# Schematic.net
KiCad netlist of a schematic drawn in EAGLE
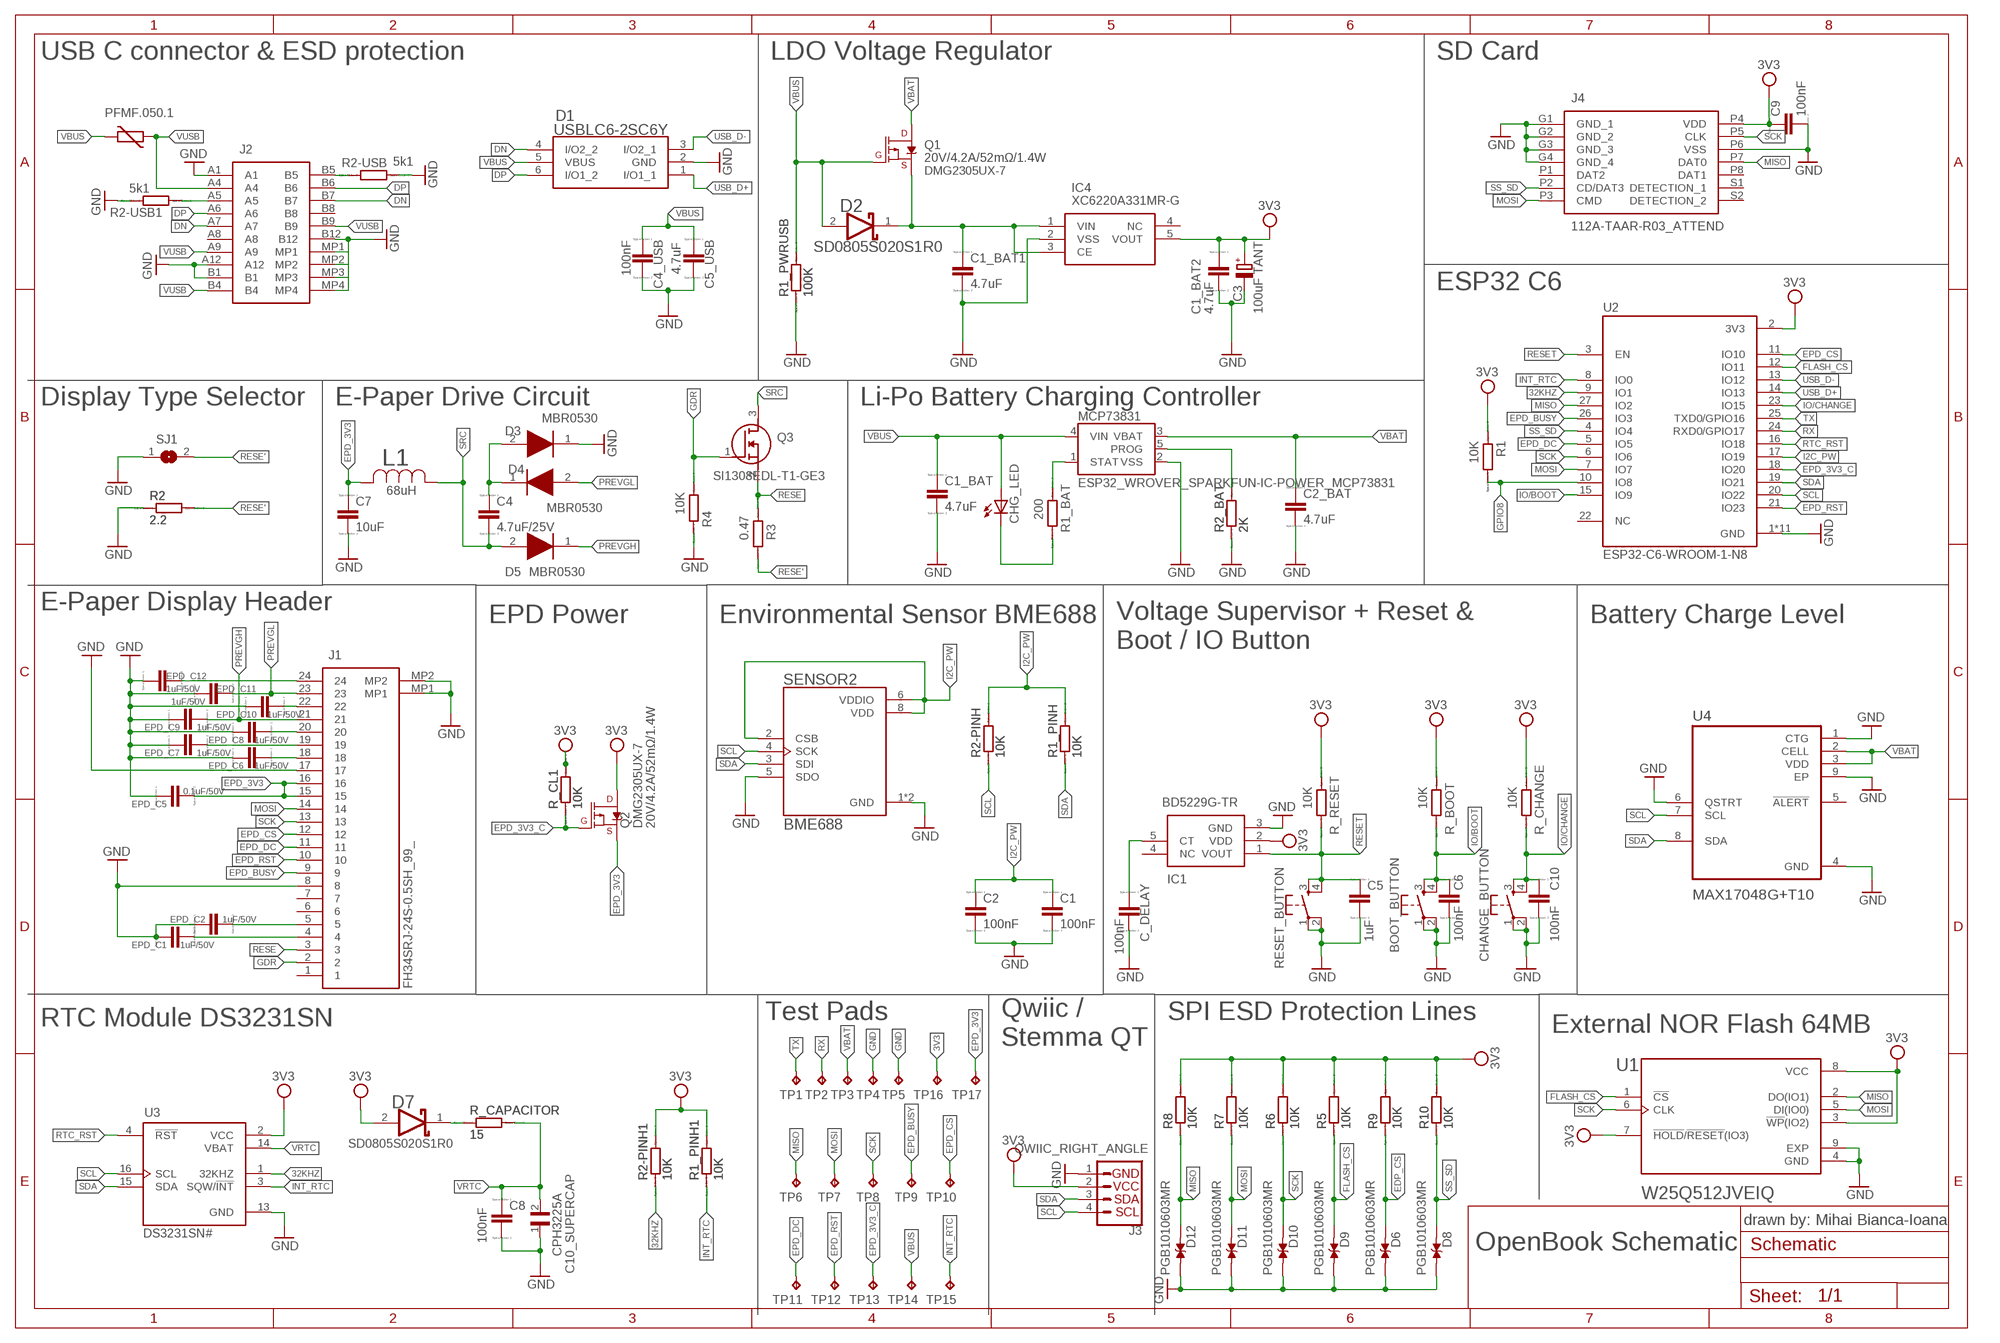
[diagram p0: schematic, sheet 1]

(export (version "E")
  (design (tool "Eeschema 10.0.6"))
  (components
    (comp (ref "BOOT_BUTTON")
      (value "BUTTON_CUSYOMV1")
      (footprint "eagle-import:MYBUTTON")
      (libsource (lib "eagle-import") (part "BUTTON_CUSYOMV1"))
    )
    (comp (ref "C1")
      (value "100nF")
      (footprint "eagle-import:ESP32_WROVER_EAGLE-LTSPICE_C0402")
      (libsource (lib "eagle-import") (part "ESP32_WROVER_EAGLE-LTSPICE_CC0402"))
    )
    (comp (ref "C1_BAT")
      (value "4.7uF")
      (footprint "eagle-import:ESP32_WROVER_EAGLE-LTSPICE_C0402")
      (libsource (lib "eagle-import") (part "ESP32_WROVER_EAGLE-LTSPICE_CC0402"))
    )
    (comp (ref "C1_BAT1")
      (value "4.7uF")
      (footprint "eagle-import:EAGLE-LTSPICE_C0402")
      (libsource (lib "eagle-import") (part "EAGLE-LTSPICE_CC0402"))
    )
    (comp (ref "C1_BAT2")
      (value "4.7uF")
      (footprint "eagle-import:EAGLE-LTSPICE_C0402")
      (libsource (lib "eagle-import") (part "EAGLE-LTSPICE_CC0402"))
    )
    (comp (ref "C2")
      (value "100nF")
      (footprint "eagle-import:ESP32_WROVER_EAGLE-LTSPICE_C0402")
      (libsource (lib "eagle-import") (part "ESP32_WROVER_EAGLE-LTSPICE_CC0402"))
    )
    (comp (ref "C2_BAT")
      (value "4.7uF")
      (footprint "eagle-import:ESP32_WROVER_EAGLE-LTSPICE_C0402")
      (libsource (lib "eagle-import") (part "ESP32_WROVER_EAGLE-LTSPICE_CC0402"))
    )
    (comp (ref "C3")
      (value "100uF TANT")
      (footprint "eagle-import:RCL_CT3528")
      (libsource (lib "eagle-import") (part "RCL_CPOL-EUCT3528"))
    )
    (comp (ref "C4")
      (value "4.7uF/25V")
      (footprint "eagle-import:ESP32_WROVER_EAGLE-LTSPICE_C0402")
      (libsource (lib "eagle-import") (part "ESP32_WROVER_EAGLE-LTSPICE_CC0402"))
    )
    (comp (ref "C4_USB")
      (value "100nF")
      (footprint "eagle-import:ESP32_WROVER_EAGLE-LTSPICE_C0402")
      (libsource (lib "eagle-import") (part "ESP32_WROVER_EAGLE-LTSPICE_CC0402"))
    )
    (comp (ref "C5")
      (value "1uF")
      (footprint "eagle-import:ESP32_WROVER_EAGLE-LTSPICE_C0402")
      (libsource (lib "eagle-import") (part "ESP32_WROVER_EAGLE-LTSPICE_CC0402"))
    )
    (comp (ref "C5_USB")
      (value "4.7uF")
      (footprint "eagle-import:ESP32_WROVER_EAGLE-LTSPICE_C0402")
      (libsource (lib "eagle-import") (part "ESP32_WROVER_EAGLE-LTSPICE_CC0402"))
    )
    (comp (ref "C6")
      (value "100nF")
      (footprint "eagle-import:ESP32_WROVER_EAGLE-LTSPICE_C0402")
      (libsource (lib "eagle-import") (part "ESP32_WROVER_EAGLE-LTSPICE_CC0402"))
    )
    (comp (ref "C7")
      (value "10uF")
      (footprint "eagle-import:ESP32_WROVER_EAGLE-LTSPICE_C0402")
      (libsource (lib "eagle-import") (part "ESP32_WROVER_EAGLE-LTSPICE_CC0402"))
    )
    (comp (ref "C8")
      (value "100nF")
      (footprint "eagle-import:ESP32_WROVER_EAGLE-LTSPICE_C0402")
      (libsource (lib "eagle-import") (part "ESP32_WROVER_EAGLE-LTSPICE_CC0402"))
    )
    (comp (ref "C9")
      (value "100nF")
      (footprint "eagle-import:ESP32_WROVER_EAGLE-LTSPICE_C0402")
      (libsource (lib "eagle-import") (part "ESP32_WROVER_EAGLE-LTSPICE_CC0402"))
    )
    (comp (ref "C10")
      (value "100nF")
      (footprint "eagle-import:ESP32_WROVER_EAGLE-LTSPICE_C0402")
      (libsource (lib "eagle-import") (part "ESP32_WROVER_EAGLE-LTSPICE_CC0402"))
    )
    (comp (ref "C10_SUPERCAP")
      (value "CPH3225A")
      (footprint "eagle-import:CAPCP3225X100N")
      (fields (field (name "MF") "Seiko Instruments"))
      (libsource (lib "eagle-import") (part "CPH3225A"))
    )
    (comp (ref "CHANGE_BUTTON")
      (value "BUTTON_CUSYOMV1")
      (footprint "eagle-import:MYBUTTON")
      (libsource (lib "eagle-import") (part "BUTTON_CUSYOMV1"))
    )
    (comp (ref "CHG_LED")
      (value "ADAFRUIT_LEDCHIP-LED0603")
      (footprint "eagle-import:ADAFRUIT_CHIP-LED0603")
      (libsource (lib "eagle-import") (part "ADAFRUIT_LEDCHIP-LED0603"))
    )
    (comp (ref "C_DELAY")
      (value "100nF")
      (footprint "eagle-import:ESP32_WROVER_EAGLE-LTSPICE_C0402")
      (libsource (lib "eagle-import") (part "ESP32_WROVER_EAGLE-LTSPICE_CC0402"))
    )
    (comp (ref "D1")
      (value "USBLC6-2SC6Y")
      (footprint "eagle-import:SOT95P280X145-6N")
      (fields
        (field (name "MF") "STMicroelectronics")
        (field (name "DETAILS") "USBLC6-2SC6Y")
        (field (name "NUME") "D1")
      )
      (libsource (lib "eagle-import") (part "USBLC6-2SC6Y"))
    )
    (comp (ref "D2")
      (value "ESP32_WROVER_AVX---SD0805S020S1R0_AVX_SD0805S020S1R0_0_0AVX_SD0805S020S1R0_0_0")
      (footprint "eagle-import:ESP32_WROVER_AVX---SD0805S020S1R0_AVX_SD0805S020S1R0_0")
      (fields
        (field (name "DIGIKEY_PART_NUMBER") "478-7800-1-ND")
        (field (name "MF") "AVX")
        (field (name "MOUSER_PART_NUMBER") "581-SD0805S020S1R0")
        (field (name "DETAILS") " SD0805S020S1R0")
      )
      (libsource (lib "eagle-import") (part "ESP32_WROVER_AVX---SD0805S020S1R0_AVX_SD0805S020S1R0_0_0AVX_SD0805S020S1R0_0_0"))
    )
    (comp (ref "D3")
      (value "MBR0530")
      (footprint "eagle-import:SOD3716X135N")
      (fields (field (name "MF") "ON Semiconductor"))
      (libsource (lib "eagle-import") (part "MBR0530"))
    )
    (comp (ref "D4")
      (value "MBR0530")
      (footprint "eagle-import:SOD3716X135N")
      (fields (field (name "MF") "ON Semiconductor"))
      (libsource (lib "eagle-import") (part "MBR0530"))
    )
    (comp (ref "D5")
      (value "MBR0530")
      (footprint "eagle-import:SOD3716X135N")
      (fields (field (name "MF") "ON Semiconductor"))
      (libsource (lib "eagle-import") (part "MBR0530"))
    )
    (comp (ref "D6")
      (value "PGB1010603MR")
      (footprint "eagle-import:DIOC1608X36N")
      (fields (field (name "MF") "Littelfuse Inc."))
      (libsource (lib "eagle-import") (part "PGB1010603MR"))
    )
    (comp (ref "D7")
      (value "ESP32_WROVER_AVX---SD0805S020S1R0_AVX_SD0805S020S1R0_0_0AVX_SD0805S020S1R0_0_0")
      (footprint "eagle-import:ESP32_WROVER_AVX---SD0805S020S1R0_AVX_SD0805S020S1R0_0")
      (fields
        (field (name "DIGIKEY_PART_NUMBER") "478-7800-1-ND")
        (field (name "MF") "AVX")
        (field (name "MOUSER_PART_NUMBER") "581-SD0805S020S1R0")
        (field (name "VALOARE") "SD0805S020S1R0")
      )
      (libsource (lib "eagle-import") (part "ESP32_WROVER_AVX---SD0805S020S1R0_AVX_SD0805S020S1R0_0_0AVX_SD0805S020S1R0_0_0"))
    )
    (comp (ref "D8")
      (value "PGB1010603MR")
      (footprint "eagle-import:DIOC1608X36N")
      (fields (field (name "MF") "Littelfuse Inc."))
      (libsource (lib "eagle-import") (part "PGB1010603MR"))
    )
    (comp (ref "D9")
      (value "PGB1010603MR")
      (footprint "eagle-import:DIOC1608X36N")
      (fields (field (name "MF") "Littelfuse Inc."))
      (libsource (lib "eagle-import") (part "PGB1010603MR"))
    )
    (comp (ref "D10")
      (value "PGB1010603MR")
      (footprint "eagle-import:DIOC1608X36N")
      (fields (field (name "MF") "Littelfuse Inc."))
      (libsource (lib "eagle-import") (part "PGB1010603MR"))
    )
    (comp (ref "D11")
      (value "PGB1010603MR")
      (footprint "eagle-import:DIOC1608X36N")
      (fields (field (name "MF") "Littelfuse Inc."))
      (libsource (lib "eagle-import") (part "PGB1010603MR"))
    )
    (comp (ref "D12")
      (value "PGB1010603MR")
      (footprint "eagle-import:DIOC1608X36N")
      (fields (field (name "MF") "Littelfuse Inc."))
      (libsource (lib "eagle-import") (part "PGB1010603MR"))
    )
    (comp (ref "EPD_C1")
      (value "1uF/50V")
      (footprint "eagle-import:ESP32_WROVER_EAGLE-LTSPICE_C0402")
      (libsource (lib "eagle-import") (part "ESP32_WROVER_EAGLE-LTSPICE_CC0402"))
    )
    (comp (ref "EPD_C2")
      (value "1uF/50V")
      (footprint "eagle-import:ESP32_WROVER_EAGLE-LTSPICE_C0402")
      (libsource (lib "eagle-import") (part "ESP32_WROVER_EAGLE-LTSPICE_CC0402"))
    )
    (comp (ref "EPD_C5")
      (value "0.1uF/50V")
      (footprint "eagle-import:ESP32_WROVER_EAGLE-LTSPICE_C0402")
      (libsource (lib "eagle-import") (part "ESP32_WROVER_EAGLE-LTSPICE_CC0402"))
    )
    (comp (ref "EPD_C6")
      (value "1uF/50V")
      (footprint "eagle-import:ESP32_WROVER_EAGLE-LTSPICE_C0402")
      (libsource (lib "eagle-import") (part "ESP32_WROVER_EAGLE-LTSPICE_CC0402"))
    )
    (comp (ref "EPD_C7")
      (value "1uF/50V")
      (footprint "eagle-import:ESP32_WROVER_EAGLE-LTSPICE_C0402")
      (libsource (lib "eagle-import") (part "ESP32_WROVER_EAGLE-LTSPICE_CC0402"))
    )
    (comp (ref "EPD_C8")
      (value "1uF/50V")
      (footprint "eagle-import:ESP32_WROVER_EAGLE-LTSPICE_C0402")
      (libsource (lib "eagle-import") (part "ESP32_WROVER_EAGLE-LTSPICE_CC0402"))
    )
    (comp (ref "EPD_C9")
      (value "1uF/50V")
      (footprint "eagle-import:ESP32_WROVER_EAGLE-LTSPICE_C0402")
      (libsource (lib "eagle-import") (part "ESP32_WROVER_EAGLE-LTSPICE_CC0402"))
    )
    (comp (ref "EPD_C10")
      (value "1uF/50V")
      (footprint "eagle-import:ESP32_WROVER_EAGLE-LTSPICE_C0402")
      (libsource (lib "eagle-import") (part "ESP32_WROVER_EAGLE-LTSPICE_CC0402"))
    )
    (comp (ref "EPD_C11")
      (value "1uF/50V")
      (footprint "eagle-import:ESP32_WROVER_EAGLE-LTSPICE_C0402")
      (libsource (lib "eagle-import") (part "ESP32_WROVER_EAGLE-LTSPICE_CC0402"))
    )
    (comp (ref "EPD_C12")
      (value "1uF/50V")
      (footprint "eagle-import:ESP32_WROVER_EAGLE-LTSPICE_C0402")
      (libsource (lib "eagle-import") (part "ESP32_WROVER_EAGLE-LTSPICE_CC0402"))
    )
    (comp (ref "IC1")
      (value "BD5229G-TR")
      (footprint "eagle-import:SOT95P280X125-5N")
      (fields (field (name "MOUSER_PART_NUMBER") "755-BD5229G-TR"))
      (libsource (lib "eagle-import") (part "BD5229G-TR"))
    )
    (comp (ref "IC4")
      (value "XC6220A331MR-G")
      (footprint "eagle-import:SOT95P280X120-5N")
      (fields (field (name "MOUSER_PART_NUMBER") "865-XC6220A331MR-G"))
      (libsource (lib "eagle-import") (part "XC6220A331MR-G"))
    )
    (comp (ref "J1")
      (value "FH34SRJ-24S-0.5SH_99_")
      (footprint "eagle-import:FH34SRJ24S05SH99")
      (fields
        (field (name "MANUFACTURER_PART_NUMBER") "FH34SRJ-24S-0.5SH(99)")
        (field (name "MOUSER_PART_NUMBER") "798-FH34SRJ24S05SH99")
      )
      (libsource (lib "eagle-import") (part "FH34SRJ-24S-0.5SH_99_"))
    )
    (comp (ref "J2")
      (value "SAMACSYS_PARTS_USB4110-GF-A")
      (footprint "eagle-import:SAMACSYS_PARTS_USB4110GFA")
      (fields
        (field (name "MANUFACTURER_PART_NUMBER") "USB4110-GF-A")
        (field (name "MOUSER_PART_NUMBER") "640-USB4110-GF-A")
      )
      (libsource (lib "eagle-import") (part "SAMACSYS_PARTS_USB4110-GF-A"))
    )
    (comp (ref "J3")
      (value "QWIIC_RIGHT_ANGLE")
      (footprint "eagle-import:JST04_1MM_RA")
      (libsource (lib "eagle-import") (part "QWIIC_CONNECTORJS-1MM"))
    )
    (comp (ref "J4")
      (value "112A-TAAR-R03_ATTEND")
      (footprint "eagle-import:112ATAARR03ATTEND")
      (fields (field (name "MANUFACTURER_PART_NUMBER") "112A-TAAR-R03 ATTEND"))
      (libsource (lib "eagle-import") (part "112A-TAAR-R03_ATTEND"))
    )
    (comp (ref "L1")
      (value "68uH")
      (footprint "eagle-import:IND_4828-WE-TPC_WRE")
      (fields
        (field (name "MANUFACTURER_PART_NUMBER") "744043680")
        (field (name "VALOARE") "68uH")
        (field (name "COPYRIGHT") "Copyright (C) 2024 Ultra Librarian. All rights reserved.")
      )
      (libsource (lib "eagle-import") (part "744043680IND_4828-WE-TPC_WRE"))
    )
    (comp (ref "MCP73831")
      (value "ESP32_WROVER_SPARKFUN-IC-POWER_MCP73831")
      (footprint "eagle-import:ESP32_WROVER_SPARKFUN-IC-POWER_SOT23-5")
      (libsource (lib "eagle-import") (part "ESP32_WROVER_SPARKFUN-IC-POWER_MCP73831"))
    )
    (comp (ref "PFMF.050.1")
      (value "ESP32C6_VARISTORCN1812")
      (footprint "eagle-import:ESP32C6_VARISTOR_CT_CN1812")
      (libsource (lib "eagle-import") (part "ESP32C6_VARISTORCN1812"))
    )
    (comp (ref "Q1")
      (value "20V/4.2A/52mΩ/1.4W")
      (footprint "eagle-import:ESP32_WROVER_SPARKFUN-DISCRETESEMI_SOT23-3")
      (fields (field (name "DETAILS") "DMG2305UX-7"))
      (libsource (lib "eagle-import") (part "ESP32_WROVER_SPARKFUN-DISCRETESEMI_MOSFET_PCH-DMG2305UX-7"))
    )
    (comp (ref "Q2")
      (value "20V/4.2A/52mΩ/1.4W")
      (footprint "eagle-import:ESP32_WROVER_SPARKFUN-DISCRETESEMI_SOT23-3")
      (fields (field (name "DETAILS") "DMG2305UX-7"))
      (libsource (lib "eagle-import") (part "ESP32_WROVER_SPARKFUN-DISCRETESEMI_MOSFET_PCH-DMG2305UX-7"))
    )
    (comp (ref "Q3")
      (value "SI1308EDL-T1-GE3")
      (footprint "eagle-import:SOT65P210X110-3N")
      (fields (field (name "MF") "Vishay Siliconix"))
      (libsource (lib "eagle-import") (part "SI1308EDL-T1-GE3"))
    )
    (comp (ref "R1")
      (value "10K")
      (footprint "eagle-import:ESP32_WROVER_EAGLE-LTSPICE_R0402")
      (libsource (lib "eagle-import") (part "ESP32_WROVER_EAGLE-LTSPICE_RR0402"))
    )
    (comp (ref "R1_BAT")
      (value "200")
      (footprint "eagle-import:ESP32_WROVER_EAGLE-LTSPICE_R0402")
      (libsource (lib "eagle-import") (part "ESP32_WROVER_EAGLE-LTSPICE_RR0402"))
    )
    (comp (ref "R1_PINH")
      (value "10K")
      (footprint "eagle-import:ESP32_WROVER_EAGLE-LTSPICE_R0402")
      (libsource (lib "eagle-import") (part "ESP32_WROVER_EAGLE-LTSPICE_RR0402"))
    )
    (comp (ref "R1_PINH1")
      (value "10K")
      (footprint "eagle-import:ESP32_WROVER_EAGLE-LTSPICE_R0402")
      (libsource (lib "eagle-import") (part "ESP32_WROVER_EAGLE-LTSPICE_RR0402"))
    )
    (comp (ref "R1_PWRUSB")
      (value "100K")
      (footprint "eagle-import:ESP32_WROVER_EAGLE-LTSPICE_R0402")
      (libsource (lib "eagle-import") (part "ESP32_WROVER_EAGLE-LTSPICE_RR0402"))
    )
    (comp (ref "R2")
      (value "2.2")
      (footprint "eagle-import:ESP32_WROVER_EAGLE-LTSPICE_R0402")
      (libsource (lib "eagle-import") (part "ESP32_WROVER_EAGLE-LTSPICE_RR0402"))
    )
    (comp (ref "R2-PINH")
      (value "10K")
      (footprint "eagle-import:ESP32_WROVER_EAGLE-LTSPICE_R0402")
      (libsource (lib "eagle-import") (part "ESP32_WROVER_EAGLE-LTSPICE_RR0402"))
    )
    (comp (ref "R2-PINH1")
      (value "10K")
      (footprint "eagle-import:ESP32_WROVER_EAGLE-LTSPICE_R0402")
      (libsource (lib "eagle-import") (part "ESP32_WROVER_EAGLE-LTSPICE_RR0402"))
    )
    (comp (ref "R2-USB")
      (value "5k1")
      (footprint "eagle-import:ESP32_WROVER_EAGLE-LTSPICE_R0402")
      (libsource (lib "eagle-import") (part "ESP32_WROVER_EAGLE-LTSPICE_RR0402"))
    )
    (comp (ref "R2-USB1")
      (value "5k1")
      (footprint "eagle-import:ESP32_WROVER_EAGLE-LTSPICE_R0402")
      (libsource (lib "eagle-import") (part "ESP32_WROVER_EAGLE-LTSPICE_RR0402"))
    )
    (comp (ref "R2_BAT")
      (value "2K")
      (footprint "eagle-import:ESP32_WROVER_EAGLE-LTSPICE_R0402")
      (libsource (lib "eagle-import") (part "ESP32_WROVER_EAGLE-LTSPICE_RR0402"))
    )
    (comp (ref "R3")
      (value "0.47")
      (footprint "eagle-import:ESP32_WROVER_EAGLE-LTSPICE_R0402")
      (libsource (lib "eagle-import") (part "ESP32_WROVER_EAGLE-LTSPICE_RR0402"))
    )
    (comp (ref "R4")
      (value "10K")
      (footprint "eagle-import:ESP32_WROVER_EAGLE-LTSPICE_R0402")
      (libsource (lib "eagle-import") (part "ESP32_WROVER_EAGLE-LTSPICE_RR0402"))
    )
    (comp (ref "R5")
      (value "10K")
      (footprint "eagle-import:ESP32_WROVER_EAGLE-LTSPICE_R0402")
      (libsource (lib "eagle-import") (part "ESP32_WROVER_EAGLE-LTSPICE_RR0402"))
    )
    (comp (ref "R6")
      (value "10K")
      (footprint "eagle-import:ESP32_WROVER_EAGLE-LTSPICE_R0402")
      (libsource (lib "eagle-import") (part "ESP32_WROVER_EAGLE-LTSPICE_RR0402"))
    )
    (comp (ref "R7")
      (value "10K")
      (footprint "eagle-import:ESP32_WROVER_EAGLE-LTSPICE_R0402")
      (libsource (lib "eagle-import") (part "ESP32_WROVER_EAGLE-LTSPICE_RR0402"))
    )
    (comp (ref "R8")
      (value "10K")
      (footprint "eagle-import:ESP32_WROVER_EAGLE-LTSPICE_R0402")
      (libsource (lib "eagle-import") (part "ESP32_WROVER_EAGLE-LTSPICE_RR0402"))
    )
    (comp (ref "R9")
      (value "10K")
      (footprint "eagle-import:ESP32_WROVER_EAGLE-LTSPICE_R0402")
      (libsource (lib "eagle-import") (part "ESP32_WROVER_EAGLE-LTSPICE_RR0402"))
    )
    (comp (ref "R10")
      (value "10K")
      (footprint "eagle-import:ESP32_WROVER_EAGLE-LTSPICE_R0402")
      (libsource (lib "eagle-import") (part "ESP32_WROVER_EAGLE-LTSPICE_RR0402"))
    )
    (comp (ref "RESET_BUTTON")
      (value "BUTTON_CUSYOMV1")
      (footprint "eagle-import:MYBUTTON")
      (libsource (lib "eagle-import") (part "BUTTON_CUSYOMV1"))
    )
    (comp (ref "R_BOOT")
      (value "10K")
      (footprint "eagle-import:ESP32_WROVER_EAGLE-LTSPICE_R0402")
      (libsource (lib "eagle-import") (part "ESP32_WROVER_EAGLE-LTSPICE_RR0402"))
    )
    (comp (ref "R_CAPACITOR")
      (value "15")
      (footprint "eagle-import:ESP32_WROVER_EAGLE-LTSPICE_R0402")
      (libsource (lib "eagle-import") (part "ESP32_WROVER_EAGLE-LTSPICE_RR0402"))
    )
    (comp (ref "R_CHANGE")
      (value "10K")
      (footprint "eagle-import:ESP32_WROVER_EAGLE-LTSPICE_R0402")
      (libsource (lib "eagle-import") (part "ESP32_WROVER_EAGLE-LTSPICE_RR0402"))
    )
    (comp (ref "R_CL1")
      (value "10K")
      (footprint "eagle-import:ESP32_WROVER_EAGLE-LTSPICE_R0402")
      (libsource (lib "eagle-import") (part "ESP32_WROVER_EAGLE-LTSPICE_RR0402"))
    )
    (comp (ref "R_RESET")
      (value "10K")
      (footprint "eagle-import:ESP32_WROVER_EAGLE-LTSPICE_R0402")
      (libsource (lib "eagle-import") (part "ESP32_WROVER_EAGLE-LTSPICE_RR0402"))
    )
    (comp (ref "SENSOR2")
      (value "BME688")
      (footprint "eagle-import:ESP32_WROVER_BME680_PSON80P300X300X100-8N")
      (fields (field (name "MF") "Bosch Sensortec") (field (name "MP") "BME680"))
      (libsource (lib "eagle-import") (part "ESP32_WROVER_BME680_BME680"))
    )
    (comp (ref "SJ1") (value "SJ") (footprint "eagle-import:SJ") (libsource (lib "eagle-import") (part "SJ")))
    (comp (ref "TP1")
      (value "TPTP20R")
      (footprint "eagle-import:TP20R")
      (libsource (lib "eagle-import") (part "TPTP20R"))
    )
    (comp (ref "TP2")
      (value "TPTP20R")
      (footprint "eagle-import:TP20R")
      (libsource (lib "eagle-import") (part "TPTP20R"))
    )
    (comp (ref "TP3")
      (value "TPTP20R")
      (footprint "eagle-import:TP20R")
      (libsource (lib "eagle-import") (part "TPTP20R"))
    )
    (comp (ref "TP4")
      (value "TPTP20R")
      (footprint "eagle-import:TP20R")
      (libsource (lib "eagle-import") (part "TPTP20R"))
    )
    (comp (ref "TP5")
      (value "TPTP20R")
      (footprint "eagle-import:TP20R")
      (libsource (lib "eagle-import") (part "TPTP20R"))
    )
    (comp (ref "TP6")
      (value "TPTP20R")
      (footprint "eagle-import:TP20R")
      (libsource (lib "eagle-import") (part "TPTP20R"))
    )
    (comp (ref "TP7")
      (value "TPTP20R")
      (footprint "eagle-import:TP20R")
      (libsource (lib "eagle-import") (part "TPTP20R"))
    )
    (comp (ref "TP8")
      (value "TPTP20R")
      (footprint "eagle-import:TP20R")
      (libsource (lib "eagle-import") (part "TPTP20R"))
    )
    (comp (ref "TP9")
      (value "TPTP20R")
      (footprint "eagle-import:TP20R")
      (libsource (lib "eagle-import") (part "TPTP20R"))
    )
    (comp (ref "TP10")
      (value "TPTP20R")
      (footprint "eagle-import:TP20R")
      (libsource (lib "eagle-import") (part "TPTP20R"))
    )
    (comp (ref "TP11")
      (value "TPTP20R")
      (footprint "eagle-import:TP20R")
      (libsource (lib "eagle-import") (part "TPTP20R"))
    )
    (comp (ref "TP12")
      (value "TPTP20R")
      (footprint "eagle-import:TP20R")
      (libsource (lib "eagle-import") (part "TPTP20R"))
    )
    (comp (ref "TP13")
      (value "TPTP20R")
      (footprint "eagle-import:TP20R")
      (libsource (lib "eagle-import") (part "TPTP20R"))
    )
    (comp (ref "TP14")
      (value "TPTP20R")
      (footprint "eagle-import:TP20R")
      (libsource (lib "eagle-import") (part "TPTP20R"))
    )
    (comp (ref "TP15")
      (value "TPTP20R")
      (footprint "eagle-import:TP20R")
      (libsource (lib "eagle-import") (part "TPTP20R"))
    )
    (comp (ref "TP16")
      (value "TPTP20R")
      (footprint "eagle-import:TP20R")
      (libsource (lib "eagle-import") (part "TPTP20R"))
    )
    (comp (ref "TP17")
      (value "TPTP20R")
      (footprint "eagle-import:TP20R")
      (libsource (lib "eagle-import") (part "TPTP20R"))
    )
    (comp (ref "U1")
      (value "W25Q512JVEIQ")
      (footprint "eagle-import:SON127P600X800X80-9N")
      (fields (field (name "MF") "Winbond Electronics"))
      (libsource (lib "eagle-import") (part "W25Q512JVEIQ"))
    )
    (comp (ref "U2")
      (value "ESP32-C6-WROOM-1-N8")
      (footprint "eagle-import:XCVR_ESP32-C6-WROOM-1-N8")
      (fields (field (name "MF") "Espressif Systems"))
      (libsource (lib "eagle-import") (part "ESP32-C6-WROOM-1-N8"))
    )
    (comp (ref "U3")
      (value "DS3231SN#")
      (footprint "eagle-import:SOIC127P1032X265-16N")
      (fields (field (name "MF") "Analog Devices"))
      (libsource (lib "eagle-import") (part "DS3231SN#"))
    )
    (comp (ref "U4")
      (value "MAX17048G+T10")
      (footprint "eagle-import:SON50P200X200X80-9N")
      (fields (field (name "MF") "Analog Devices"))
      (libsource (lib "eagle-import") (part "MAX17048G+T10"))
    )
  )
  (nets
    (net (code "1") (name "3V3") (class "Default")
      (node (ref "C1_BAT2") (pin "1") (pinfunction "1_1") (pintype "passive"))
      (node (ref "C3") (pin "+") (pinfunction "+_+") (pintype "passive"))
      (node (ref "C9") (pin "1") (pinfunction "1_1") (pintype "passive"))
      (node (ref "D7") (pin "2") (pinfunction "ANODE_2") (pintype "bidirectional"))
      (node (ref "IC1") (pin "2") (pinfunction "VDD_2") (pintype "bidirectional"))
      (node (ref "IC4") (pin "5") (pinfunction "VOUT_5") (pintype "bidirectional"))
      (node (ref "J3") (pin "2") (pinfunction "2_2") (pintype "power_in"))
      (node (ref "J4") (pin "P4") (pinfunction "VDD_P4") (pintype "bidirectional"))
      (node (ref "Q2") (pin "3") (pinfunction "D_3") (pintype "bidirectional"))
      (node (ref "R1") (pin "2") (pinfunction "2_2") (pintype "passive"))
      (node (ref "R10") (pin "2") (pinfunction "2_2") (pintype "passive"))
      (node (ref "R1_PINH1") (pin "2") (pinfunction "2_2") (pintype "passive"))
      (node (ref "R2-PINH1") (pin "2") (pinfunction "2_2") (pintype "passive"))
      (node (ref "R5") (pin "2") (pinfunction "2_2") (pintype "passive"))
      (node (ref "R6") (pin "2") (pinfunction "2_2") (pintype "passive"))
      (node (ref "R7") (pin "2") (pinfunction "2_2") (pintype "passive"))
      (node (ref "R8") (pin "2") (pinfunction "2_2") (pintype "passive"))
      (node (ref "R9") (pin "2") (pinfunction "2_2") (pintype "passive"))
      (node (ref "R_BOOT") (pin "2") (pinfunction "2_2") (pintype "passive"))
      (node (ref "R_CHANGE") (pin "2") (pinfunction "2_2") (pintype "passive"))
      (node (ref "R_CL1") (pin "2") (pinfunction "2_2") (pintype "passive"))
      (node (ref "R_RESET") (pin "2") (pinfunction "2_2") (pintype "passive"))
      (node (ref "TP16") (pin "TP") (pinfunction "TP_TP") (pintype "input"))
      (node (ref "U1") (pin "3") (pinfunction "~{WP}(IO2)_3") (pintype "bidirectional"))
      (node (ref "U1") (pin "7") (pinfunction "~{HOLD}/~{RESET}(IO3)_7") (pintype "bidirectional"))
      (node (ref "U1") (pin "8") (pinfunction "VCC_8") (pintype "power_in"))
      (node (ref "U2") (pin "2") (pinfunction "3V3_2") (pintype "power_in"))
      (node (ref "U3") (pin "2") (pinfunction "VCC_2") (pintype "power_in"))
    )
    (net (code "2") (name "32KHZ") (class "Default")
      (node (ref "R2-PINH1") (pin "1") (pinfunction "1_1") (pintype "passive"))
      (node (ref "U2") (pin "9") (pinfunction "IO1_9") (pintype "bidirectional"))
      (node (ref "U3") (pin "1") (pinfunction "32KHZ_1") (pintype "output"))
    )
    (net (code "3") (name "DN") (class "Default")
      (node (ref "D1") (pin "4") (pinfunction "I/O2_2_4") (pintype "bidirectional"))
      (node (ref "J2") (pin "A7") (pinfunction "A7_A7") (pintype "bidirectional"))
      (node (ref "J2") (pin "B7") (pinfunction "B7_B7") (pintype "bidirectional"))
    )
    (net (code "4") (name "DP") (class "Default")
      (node (ref "D1") (pin "6") (pinfunction "I/O1_2_6") (pintype "bidirectional"))
      (node (ref "J2") (pin "A6") (pinfunction "A6_A6") (pintype "bidirectional"))
      (node (ref "J2") (pin "B6") (pinfunction "B6_B6") (pintype "bidirectional"))
    )
    (net (code "5") (name "EDP_CS") (class "Default")
      (node (ref "D6") (pin "1") (pinfunction "1_1") (pintype "passive"))
      (node (ref "R9") (pin "1") (pinfunction "1_1") (pintype "passive"))
    )
    (net (code "6") (name "EPD_3V3") (class "Default")
      (node (ref "C7") (pin "1") (pinfunction "1_1") (pintype "passive"))
      (node (ref "EPD_C5") (pin "2") (pinfunction "2_2") (pintype "passive"))
      (node (ref "J1") (pin "15") (pinfunction "15_15") (pintype "bidirectional"))
      (node (ref "J1") (pin "16") (pinfunction "16_16") (pintype "bidirectional"))
      (node (ref "L1") (pin "2") (pinfunction "2_2") (pintype "passive"))
      (node (ref "Q2") (pin "2") (pinfunction "S_2") (pintype "bidirectional"))
      (node (ref "TP17") (pin "TP") (pinfunction "TP_TP") (pintype "input"))
    )
    (net (code "7") (name "EPD_3V3_C") (class "Default")
      (node (ref "Q2") (pin "1") (pinfunction "G_1") (pintype "bidirectional"))
      (node (ref "R_CL1") (pin "1") (pinfunction "1_1") (pintype "passive"))
      (node (ref "TP13") (pin "TP") (pinfunction "TP_TP") (pintype "input"))
      (node (ref "U2") (pin "18") (pinfunction "IO20_18") (pintype "bidirectional"))
    )
    (net (code "8") (name "EPD_BUSY") (class "Default")
      (node (ref "J1") (pin "9") (pinfunction "9_9") (pintype "bidirectional"))
      (node (ref "TP9") (pin "TP") (pinfunction "TP_TP") (pintype "input"))
      (node (ref "U2") (pin "26") (pinfunction "IO3_26") (pintype "bidirectional"))
    )
    (net (code "9") (name "EPD_CS") (class "Default")
      (node (ref "J1") (pin "12") (pinfunction "12_12") (pintype "bidirectional"))
      (node (ref "TP10") (pin "TP") (pinfunction "TP_TP") (pintype "input"))
      (node (ref "U2") (pin "11") (pinfunction "IO10_11") (pintype "bidirectional"))
    )
    (net (code "10") (name "EPD_DC") (class "Default")
      (node (ref "J1") (pin "11") (pinfunction "11_11") (pintype "bidirectional"))
      (node (ref "TP11") (pin "TP") (pinfunction "TP_TP") (pintype "input"))
      (node (ref "U2") (pin "5") (pinfunction "IO5_5") (pintype "bidirectional"))
    )
    (net (code "11") (name "EPD_RST") (class "Default")
      (node (ref "J1") (pin "10") (pinfunction "10_10") (pintype "bidirectional"))
      (node (ref "TP12") (pin "TP") (pinfunction "TP_TP") (pintype "input"))
      (node (ref "U2") (pin "21") (pinfunction "IO23_21") (pintype "bidirectional"))
    )
    (net (code "12") (name "FLASH_CS") (class "Default")
      (node (ref "D9") (pin "1") (pinfunction "1_1") (pintype "passive"))
      (node (ref "R5") (pin "1") (pinfunction "1_1") (pintype "passive"))
      (node (ref "U1") (pin "1") (pinfunction "~{CS}_1") (pintype "input"))
      (node (ref "U2") (pin "12") (pinfunction "IO11_12") (pintype "bidirectional"))
    )
    (net (code "13") (name "GDR") (class "Default")
      (node (ref "J1") (pin "2") (pinfunction "2_2") (pintype "bidirectional"))
      (node (ref "Q3") (pin "1") (pinfunction "G_1") (pintype "bidirectional"))
      (node (ref "R4") (pin "2") (pinfunction "2_2") (pintype "passive"))
    )
    (net (code "14") (name "GND") (class "Default")
      (node (ref "BOOT_BUTTON") (pin "1") (pinfunction "1_1") (pintype "passive"))
      (node (ref "BOOT_BUTTON") (pin "2") (pinfunction "2_2") (pintype "passive"))
      (node (ref "C1") (pin "2") (pinfunction "2_2") (pintype "passive"))
      (node (ref "C10") (pin "2") (pinfunction "2_2") (pintype "passive"))
      (node (ref "C10_SUPERCAP") (pin "1") (pinfunction "1_1") (pintype "passive"))
      (node (ref "C1_BAT") (pin "2") (pinfunction "2_2") (pintype "passive"))
      (node (ref "C1_BAT1") (pin "2") (pinfunction "2_2") (pintype "passive"))
      (node (ref "C1_BAT2") (pin "2") (pinfunction "2_2") (pintype "passive"))
      (node (ref "C2") (pin "2") (pinfunction "2_2") (pintype "passive"))
      (node (ref "C2_BAT") (pin "2") (pinfunction "2_2") (pintype "passive"))
      (node (ref "C3") (pin "-") (pinfunction "-_-") (pintype "passive"))
      (node (ref "C4_USB") (pin "2") (pinfunction "2_2") (pintype "passive"))
      (node (ref "C5") (pin "2") (pinfunction "2_2") (pintype "passive"))
      (node (ref "C5_USB") (pin "2") (pinfunction "2_2") (pintype "passive"))
      (node (ref "C6") (pin "2") (pinfunction "2_2") (pintype "passive"))
      (node (ref "C7") (pin "2") (pinfunction "2_2") (pintype "passive"))
      (node (ref "C8") (pin "2") (pinfunction "2_2") (pintype "passive"))
      (node (ref "C9") (pin "2") (pinfunction "2_2") (pintype "passive"))
      (node (ref "CHANGE_BUTTON") (pin "1") (pinfunction "1_1") (pintype "passive"))
      (node (ref "CHANGE_BUTTON") (pin "2") (pinfunction "2_2") (pintype "passive"))
      (node (ref "C_DELAY") (pin "2") (pinfunction "2_2") (pintype "passive"))
      (node (ref "D1") (pin "2") (pinfunction "GND_2") (pintype "bidirectional"))
      (node (ref "D10") (pin "2") (pinfunction "2_2") (pintype "passive"))
      (node (ref "D11") (pin "2") (pinfunction "2_2") (pintype "passive"))
      (node (ref "D12") (pin "2") (pinfunction "2_2") (pintype "passive"))
      (node (ref "D3") (pin "1") (pinfunction "K_1") (pintype "bidirectional"))
      (node (ref "D6") (pin "2") (pinfunction "2_2") (pintype "passive"))
      (node (ref "D8") (pin "2") (pinfunction "2_2") (pintype "passive"))
      (node (ref "D9") (pin "2") (pinfunction "2_2") (pintype "passive"))
      (node (ref "EPD_C1") (pin "1") (pinfunction "1_1") (pintype "passive"))
      (node (ref "EPD_C10") (pin "1") (pinfunction "1_1") (pintype "passive"))
      (node (ref "EPD_C11") (pin "1") (pinfunction "1_1") (pintype "passive"))
      (node (ref "EPD_C12") (pin "1") (pinfunction "1_1") (pintype "passive"))
      (node (ref "EPD_C2") (pin "1") (pinfunction "1_1") (pintype "passive"))
      (node (ref "EPD_C5") (pin "1") (pinfunction "1_1") (pintype "passive"))
      (node (ref "EPD_C6") (pin "1") (pinfunction "1_1") (pintype "passive"))
      (node (ref "EPD_C7") (pin "1") (pinfunction "1_1") (pintype "passive"))
      (node (ref "EPD_C8") (pin "1") (pinfunction "1_1") (pintype "passive"))
      (node (ref "EPD_C9") (pin "1") (pinfunction "1_1") (pintype "passive"))
      (node (ref "IC1") (pin "3") (pinfunction "GND_3") (pintype "bidirectional"))
      (node (ref "IC4") (pin "2") (pinfunction "VSS_2") (pintype "bidirectional"))
      (node (ref "J1") (pin "17") (pinfunction "17_17") (pintype "bidirectional"))
      (node (ref "J1") (pin "8") (pinfunction "8_8") (pintype "bidirectional"))
      (node (ref "J1") (pin "MP1") (pinfunction "MP1_MP1") (pintype "bidirectional"))
      (node (ref "J1") (pin "MP2") (pinfunction "MP2_MP2") (pintype "bidirectional"))
      (node (ref "J2") (pin "A1") (pinfunction "A1_A1") (pintype "bidirectional"))
      (node (ref "J2") (pin "A12") (pinfunction "A12_A12") (pintype "bidirectional"))
      (node (ref "J2") (pin "B1") (pinfunction "B1_B1") (pintype "bidirectional"))
      (node (ref "J2") (pin "B12") (pinfunction "B12_B12") (pintype "bidirectional"))
      (node (ref "J2") (pin "MP1") (pinfunction "MP1_MP1") (pintype "bidirectional"))
      (node (ref "J2") (pin "MP2") (pinfunction "MP2_MP2") (pintype "bidirectional"))
      (node (ref "J2") (pin "MP3") (pinfunction "MP3_MP3") (pintype "bidirectional"))
      (node (ref "J2") (pin "MP4") (pinfunction "MP4_MP4") (pintype "bidirectional"))
      (node (ref "J3") (pin "1") (pinfunction "1_1") (pintype "power_in"))
      (node (ref "J4") (pin "G1") (pinfunction "GND_1_G1") (pintype "bidirectional"))
      (node (ref "J4") (pin "G2") (pinfunction "GND_2_G2") (pintype "bidirectional"))
      (node (ref "J4") (pin "G3") (pinfunction "GND_3_G3") (pintype "bidirectional"))
      (node (ref "J4") (pin "G4") (pinfunction "GND_4_G4") (pintype "bidirectional"))
      (node (ref "J4") (pin "P6") (pinfunction "VSS_P6") (pintype "bidirectional"))
      (node (ref "MCP73831") (pin "2") (pinfunction "VSS_2") (pintype "power_in"))
      (node (ref "R1_PWRUSB") (pin "1") (pinfunction "1_1") (pintype "passive"))
      (node (ref "R2") (pin "1") (pinfunction "1_1") (pintype "passive"))
      (node (ref "R2-USB") (pin "2") (pinfunction "2_2") (pintype "passive"))
      (node (ref "R2-USB1") (pin "2") (pinfunction "2_2") (pintype "passive"))
      (node (ref "R2_BAT") (pin "1") (pinfunction "1_1") (pintype "passive"))
      (node (ref "R4") (pin "1") (pinfunction "1_1") (pintype "passive"))
      (node (ref "RESET_BUTTON") (pin "1") (pinfunction "1_1") (pintype "passive"))
      (node (ref "RESET_BUTTON") (pin "2") (pinfunction "2_2") (pintype "passive"))
      (node (ref "SENSOR2") (pin "1") (pinfunction "GND_1") (pintype "power_in"))
      (node (ref "SENSOR2") (pin "5") (pinfunction "SDO_5") (pintype "bidirectional"))
      (node (ref "SENSOR2") (pin "7") (pinfunction "GND_7") (pintype "power_in"))
      (node (ref "SJ1") (pin "1") (pinfunction "1_1") (pintype "passive"))
      (node (ref "TP4") (pin "TP") (pinfunction "TP_TP") (pintype "input"))
      (node (ref "TP5") (pin "TP") (pinfunction "TP_TP") (pintype "input"))
      (node (ref "U1") (pin "4") (pinfunction "GND_4") (pintype "power_in"))
      (node (ref "U1") (pin "9") (pinfunction "EXP_9") (pintype "passive"))
      (node (ref "U2") (pin "1") (pinfunction "GND_1") (pintype "power_in"))
      (node (ref "U2") (pin "28") (pinfunction "GND_28") (pintype "power_in"))
      (node (ref "U2") (pin "29_1") (pinfunction "GND_29_1") (pintype "power_in"))
      (node (ref "U2") (pin "29_2") (pinfunction "GND_29_2") (pintype "power_in"))
      (node (ref "U2") (pin "29_3") (pinfunction "GND_29_3") (pintype "power_in"))
      (node (ref "U2") (pin "29_4") (pinfunction "GND_29_4") (pintype "power_in"))
      (node (ref "U2") (pin "29_5") (pinfunction "GND_29_5") (pintype "power_in"))
      (node (ref "U2") (pin "29_6") (pinfunction "GND_29_6") (pintype "power_in"))
      (node (ref "U2") (pin "29_7") (pinfunction "GND_29_7") (pintype "power_in"))
      (node (ref "U2") (pin "29_8") (pinfunction "GND_29_8") (pintype "power_in"))
      (node (ref "U2") (pin "29_9") (pinfunction "GND_29_9") (pintype "power_in"))
      (node (ref "U3") (pin "13") (pinfunction "GND_13") (pintype "power_in"))
      (node (ref "U4") (pin "1") (pinfunction "CTG_1") (pintype "power_in"))
      (node (ref "U4") (pin "4") (pinfunction "GND_4") (pintype "power_in"))
      (node (ref "U4") (pin "6") (pinfunction "QSTRT_6") (pintype "input"))
      (node (ref "U4") (pin "9") (pinfunction "EP_9") (pintype "power_in"))
    )
    (net (code "15") (name "GPIO8") (class "Default")
      (node (ref "R1") (pin "1") (pinfunction "1_1") (pintype "passive"))
      (node (ref "U2") (pin "10") (pinfunction "IO8_10") (pintype "bidirectional"))
    )
    (net (code "16") (name "I2C_PW") (class "Default")
      (node (ref "C1") (pin "1") (pinfunction "1_1") (pintype "passive"))
      (node (ref "C2") (pin "1") (pinfunction "1_1") (pintype "passive"))
      (node (ref "R1_PINH") (pin "2") (pinfunction "2_2") (pintype "passive"))
      (node (ref "R2-PINH") (pin "2") (pinfunction "2_2") (pintype "passive"))
      (node (ref "SENSOR2") (pin "2") (pinfunction "CSB_2") (pintype "input"))
      (node (ref "SENSOR2") (pin "6") (pinfunction "VDDIO_6") (pintype "power_in"))
      (node (ref "SENSOR2") (pin "8") (pinfunction "VDD_8") (pintype "power_in"))
      (node (ref "U2") (pin "17") (pinfunction "IO19_17") (pintype "bidirectional"))
    )
    (net (code "17") (name "INT_RTC") (class "Default")
      (node (ref "R1_PINH1") (pin "1") (pinfunction "1_1") (pintype "passive"))
      (node (ref "TP15") (pin "TP") (pinfunction "TP_TP") (pintype "input"))
      (node (ref "U2") (pin "8") (pinfunction "IO0_8") (pintype "bidirectional"))
      (node (ref "U3") (pin "3") (pinfunction "SQW/~{INT}_3") (pintype "output"))
    )
    (net (code "18") (name "IO{slash}BOOT") (class "Default")
      (node (ref "BOOT_BUTTON") (pin "3") (pinfunction "3_3") (pintype "passive"))
      (node (ref "BOOT_BUTTON") (pin "4") (pinfunction "4_4") (pintype "passive"))
      (node (ref "C6") (pin "1") (pinfunction "1_1") (pintype "passive"))
      (node (ref "R_BOOT") (pin "1") (pinfunction "1_1") (pintype "passive"))
      (node (ref "U2") (pin "15") (pinfunction "IO9_15") (pintype "bidirectional"))
    )
    (net (code "19") (name "IO{slash}CHANGE") (class "Default")
      (node (ref "C10") (pin "1") (pinfunction "1_1") (pintype "passive"))
      (node (ref "CHANGE_BUTTON") (pin "3") (pinfunction "3_3") (pintype "passive"))
      (node (ref "CHANGE_BUTTON") (pin "4") (pinfunction "4_4") (pintype "passive"))
      (node (ref "R_CHANGE") (pin "1") (pinfunction "1_1") (pintype "passive"))
      (node (ref "U2") (pin "23") (pinfunction "IO15_23") (pintype "bidirectional"))
    )
    (net (code "20") (name "MISO") (class "Default")
      (node (ref "D12") (pin "1") (pinfunction "1_1") (pintype "passive"))
      (node (ref "J4") (pin "P7") (pinfunction "DAT0_P7") (pintype "bidirectional"))
      (node (ref "R8") (pin "1") (pinfunction "1_1") (pintype "passive"))
      (node (ref "TP6") (pin "TP") (pinfunction "TP_TP") (pintype "input"))
      (node (ref "U1") (pin "2") (pinfunction "DO(IO1)_2") (pintype "bidirectional"))
      (node (ref "U2") (pin "27") (pinfunction "IO2_27") (pintype "bidirectional"))
    )
    (net (code "21") (name "MOSI") (class "Default")
      (node (ref "D11") (pin "1") (pinfunction "1_1") (pintype "passive"))
      (node (ref "J1") (pin "14") (pinfunction "14_14") (pintype "bidirectional"))
      (node (ref "J4") (pin "P3") (pinfunction "CMD_P3") (pintype "bidirectional"))
      (node (ref "R7") (pin "1") (pinfunction "1_1") (pintype "passive"))
      (node (ref "TP7") (pin "TP") (pinfunction "TP_TP") (pintype "input"))
      (node (ref "U1") (pin "5") (pinfunction "DI(IO0)_5") (pintype "bidirectional"))
      (node (ref "U2") (pin "7") (pinfunction "IO7_7") (pintype "bidirectional"))
    )
    (net (code "22") (name "Net-(CHG_LED-PadC)") (class "Default")
      (node (ref "CHG_LED") (pin "C") (pinfunction "C_C") (pintype "passive"))
      (node (ref "R1_BAT") (pin "1") (pinfunction "1_1") (pintype "passive"))
    )
    (net (code "23") (name "Net-(D2-CATHODE)") (class "Default")
      (node (ref "C1_BAT1") (pin "1") (pinfunction "1_1") (pintype "passive"))
      (node (ref "D2") (pin "1") (pinfunction "CATHODE_1") (pintype "bidirectional"))
      (node (ref "IC4") (pin "1") (pinfunction "VIN_1") (pintype "bidirectional"))
      (node (ref "IC4") (pin "3") (pinfunction "CE_3") (pintype "bidirectional"))
      (node (ref "Q1") (pin "2") (pinfunction "S_2") (pintype "bidirectional"))
    )
    (net (code "24") (name "Net-(D3-A)") (class "Default")
      (node (ref "C4") (pin "1") (pinfunction "1_1") (pintype "passive"))
      (node (ref "D3") (pin "2") (pinfunction "A_2") (pintype "bidirectional"))
      (node (ref "D4") (pin "1") (pinfunction "K_1") (pintype "bidirectional"))
    )
    (net (code "25") (name "Net-(D7-CATHODE)") (class "Default")
      (node (ref "D7") (pin "1") (pinfunction "CATHODE_1") (pintype "bidirectional"))
      (node (ref "R_CAPACITOR") (pin "1") (pinfunction "1_1") (pintype "passive"))
    )
    (net (code "26") (name "Net-(EPD_C1-Pad2)") (class "Default")
      (node (ref "EPD_C1") (pin "2") (pinfunction "2_2") (pintype "passive"))
      (node (ref "J1") (pin "4") (pinfunction "4_4") (pintype "bidirectional"))
    )
    (net (code "27") (name "Net-(EPD_C2-Pad2)") (class "Default")
      (node (ref "EPD_C2") (pin "2") (pinfunction "2_2") (pintype "passive"))
      (node (ref "J1") (pin "5") (pinfunction "5_5") (pintype "bidirectional"))
    )
    (net (code "28") (name "Net-(EPD_C6-Pad2)") (class "Default")
      (node (ref "EPD_C6") (pin "2") (pinfunction "2_2") (pintype "passive"))
      (node (ref "J1") (pin "18") (pinfunction "18_18") (pintype "bidirectional"))
    )
    (net (code "29") (name "Net-(EPD_C7-Pad2)") (class "Default")
      (node (ref "EPD_C7") (pin "2") (pinfunction "2_2") (pintype "passive"))
      (node (ref "J1") (pin "19") (pinfunction "19_19") (pintype "bidirectional"))
    )
    (net (code "30") (name "Net-(EPD_C8-Pad2)") (class "Default")
      (node (ref "EPD_C8") (pin "2") (pinfunction "2_2") (pintype "passive"))
      (node (ref "J1") (pin "20") (pinfunction "20_20") (pintype "bidirectional"))
    )
    (net (code "31") (name "Net-(EPD_C10-Pad2)") (class "Default")
      (node (ref "EPD_C10") (pin "2") (pinfunction "2_2") (pintype "passive"))
      (node (ref "J1") (pin "22") (pinfunction "22_22") (pintype "bidirectional"))
    )
    (net (code "32") (name "Net-(EPD_C12-Pad2)") (class "Default")
      (node (ref "EPD_C12") (pin "2") (pinfunction "2_2") (pintype "passive"))
      (node (ref "J1") (pin "24") (pinfunction "24_24") (pintype "bidirectional"))
    )
    (net (code "33") (name "Net-(IC1-CT)") (class "Default")
      (node (ref "C_DELAY") (pin "1") (pinfunction "1_1") (pintype "passive"))
      (node (ref "IC1") (pin "5") (pinfunction "CT_5") (pintype "bidirectional"))
    )
    (net (code "34") (name "Net-(J2-PadA5)") (class "Default")
      (node (ref "J2") (pin "A5") (pinfunction "A5_A5") (pintype "bidirectional"))
      (node (ref "R2-USB1") (pin "1") (pinfunction "1_1") (pintype "passive"))
    )
    (net (code "35") (name "Net-(J2-PadB5)") (class "Default")
      (node (ref "J2") (pin "B5") (pinfunction "B5_B5") (pintype "bidirectional"))
      (node (ref "R2-USB") (pin "1") (pinfunction "1_1") (pintype "passive"))
    )
    (net (code "36") (name "Net-(MCP73831-PROG)") (class "Default")
      (node (ref "MCP73831") (pin "5") (pinfunction "PROG_5") (pintype "input"))
      (node (ref "R2_BAT") (pin "2") (pinfunction "2_2") (pintype "passive"))
    )
    (net (code "37") (name "Net-(MCP73831-STAT)") (class "Default")
      (node (ref "MCP73831") (pin "1") (pinfunction "STAT_1") (pintype "output"))
      (node (ref "R1_BAT") (pin "2") (pinfunction "2_2") (pintype "passive"))
    )
    (net (code "38") (name "PREVGH") (class "Default")
      (node (ref "D5") (pin "1") (pinfunction "K_1") (pintype "bidirectional"))
      (node (ref "EPD_C9") (pin "2") (pinfunction "2_2") (pintype "passive"))
      (node (ref "J1") (pin "21") (pinfunction "21_21") (pintype "bidirectional"))
    )
    (net (code "39") (name "PREVGL") (class "Default")
      (node (ref "D4") (pin "2") (pinfunction "A_2") (pintype "bidirectional"))
      (node (ref "EPD_C11") (pin "2") (pinfunction "2_2") (pintype "passive"))
      (node (ref "J1") (pin "23") (pinfunction "23_23") (pintype "bidirectional"))
    )
    (net (code "40") (name "RESE") (class "Default")
      (node (ref "J1") (pin "3") (pinfunction "3_3") (pintype "bidirectional"))
      (node (ref "Q3") (pin "2") (pinfunction "S_2") (pintype "bidirectional"))
      (node (ref "R3") (pin "2") (pinfunction "2_2") (pintype "passive"))
    )
    (net (code "41") (name "RESE'") (class "Default")
      (node (ref "R2") (pin "2") (pinfunction "2_2") (pintype "passive"))
      (node (ref "R3") (pin "1") (pinfunction "1_1") (pintype "passive"))
      (node (ref "SJ1") (pin "2") (pinfunction "2_2") (pintype "passive"))
    )
    (net (code "42") (name "RESET") (class "Default")
      (node (ref "C5") (pin "1") (pinfunction "1_1") (pintype "passive"))
      (node (ref "IC1") (pin "1") (pinfunction "VOUT_1") (pintype "bidirectional"))
      (node (ref "RESET_BUTTON") (pin "3") (pinfunction "3_3") (pintype "passive"))
      (node (ref "RESET_BUTTON") (pin "4") (pinfunction "4_4") (pintype "passive"))
      (node (ref "R_RESET") (pin "1") (pinfunction "1_1") (pintype "passive"))
      (node (ref "U2") (pin "3") (pinfunction "EN_3") (pintype "input"))
    )
    (net (code "43") (name "RTC_RST") (class "Default")
      (node (ref "U2") (pin "16") (pinfunction "IO18_16") (pintype "bidirectional"))
      (node (ref "U3") (pin "4") (pinfunction "~{RST}_4") (pintype "input"))
    )
    (net (code "44") (name "RX") (class "Default")
      (node (ref "TP2") (pin "TP") (pinfunction "TP_TP") (pintype "input"))
      (node (ref "U2") (pin "24") (pinfunction "RXD0/GPIO17_24") (pintype "bidirectional"))
    )
    (net (code "45") (name "SCK") (class "Default")
      (node (ref "D10") (pin "1") (pinfunction "1_1") (pintype "passive"))
      (node (ref "J1") (pin "13") (pinfunction "13_13") (pintype "bidirectional"))
      (node (ref "J4") (pin "P5") (pinfunction "CLK_P5") (pintype "bidirectional"))
      (node (ref "R6") (pin "1") (pinfunction "1_1") (pintype "passive"))
      (node (ref "TP8") (pin "TP") (pinfunction "TP_TP") (pintype "input"))
      (node (ref "U1") (pin "6") (pinfunction "CLK_6") (pintype "input"))
      (node (ref "U2") (pin "6") (pinfunction "IO6_6") (pintype "bidirectional"))
    )
    (net (code "46") (name "SCL") (class "Default")
      (node (ref "J3") (pin "4") (pinfunction "4_4") (pintype "passive"))
      (node (ref "R2-PINH") (pin "1") (pinfunction "1_1") (pintype "passive"))
      (node (ref "SENSOR2") (pin "4") (pinfunction "SCK_4") (pintype "input"))
      (node (ref "U2") (pin "20") (pinfunction "IO22_20") (pintype "bidirectional"))
      (node (ref "U3") (pin "16") (pinfunction "SCL_16") (pintype "input"))
      (node (ref "U4") (pin "7") (pinfunction "SCL_7") (pintype "input"))
    )
    (net (code "47") (name "SDA") (class "Default")
      (node (ref "J3") (pin "3") (pinfunction "3_3") (pintype "passive"))
      (node (ref "R1_PINH") (pin "1") (pinfunction "1_1") (pintype "passive"))
      (node (ref "SENSOR2") (pin "3") (pinfunction "SDI_3") (pintype "bidirectional"))
      (node (ref "U2") (pin "19") (pinfunction "IO21_19") (pintype "bidirectional"))
      (node (ref "U3") (pin "15") (pinfunction "SDA_15") (pintype "bidirectional"))
      (node (ref "U4") (pin "8") (pinfunction "SDA_8") (pintype "bidirectional"))
    )
    (net (code "48") (name "SRC") (class "Default")
      (node (ref "C4") (pin "2") (pinfunction "2_2") (pintype "passive"))
      (node (ref "D5") (pin "2") (pinfunction "A_2") (pintype "bidirectional"))
      (node (ref "L1") (pin "1") (pinfunction "1_1") (pintype "passive"))
      (node (ref "Q3") (pin "3") (pinfunction "D_3") (pintype "bidirectional"))
    )
    (net (code "49") (name "SS_SD") (class "Default")
      (node (ref "D8") (pin "1") (pinfunction "1_1") (pintype "passive"))
      (node (ref "J4") (pin "P2") (pinfunction "CD/DAT3_P2") (pintype "bidirectional"))
      (node (ref "R10") (pin "1") (pinfunction "1_1") (pintype "passive"))
      (node (ref "U2") (pin "4") (pinfunction "IO4_4") (pintype "bidirectional"))
    )
    (net (code "50") (name "TX") (class "Default")
      (node (ref "TP1") (pin "TP") (pinfunction "TP_TP") (pintype "input"))
      (node (ref "U2") (pin "25") (pinfunction "TXD0/GPIO16_25") (pintype "bidirectional"))
    )
    (net (code "51") (name "USB_D+") (class "Default")
      (node (ref "D1") (pin "1") (pinfunction "I/O1_1_1") (pintype "bidirectional"))
      (node (ref "U2") (pin "14") (pinfunction "IO13_14") (pintype "bidirectional"))
    )
    (net (code "52") (name "USB_D-") (class "Default")
      (node (ref "D1") (pin "3") (pinfunction "I/O2_1_3") (pintype "bidirectional"))
      (node (ref "U2") (pin "13") (pinfunction "IO12_13") (pintype "bidirectional"))
    )
    (net (code "53") (name "VBAT") (class "Default")
      (node (ref "C2_BAT") (pin "1") (pinfunction "1_1") (pintype "passive"))
      (node (ref "MCP73831") (pin "3") (pinfunction "VBAT_3") (pintype "power_in"))
      (node (ref "Q1") (pin "3") (pinfunction "D_3") (pintype "bidirectional"))
      (node (ref "TP3") (pin "TP") (pinfunction "TP_TP") (pintype "input"))
      (node (ref "U4") (pin "2") (pinfunction "CELL_2") (pintype "power_in"))
      (node (ref "U4") (pin "3") (pinfunction "VDD_3") (pintype "power_in"))
    )
    (net (code "54") (name "VBUS") (class "Default")
      (node (ref "C1_BAT") (pin "1") (pinfunction "1_1") (pintype "passive"))
      (node (ref "C4_USB") (pin "1") (pinfunction "1_1") (pintype "passive"))
      (node (ref "C5_USB") (pin "1") (pinfunction "1_1") (pintype "passive"))
      (node (ref "CHG_LED") (pin "A") (pinfunction "A_A") (pintype "passive"))
      (node (ref "D1") (pin "5") (pinfunction "VBUS_5") (pintype "bidirectional"))
      (node (ref "D2") (pin "2") (pinfunction "ANODE_2") (pintype "bidirectional"))
      (node (ref "MCP73831") (pin "4") (pinfunction "VIN_4") (pintype "power_in"))
      (node (ref "PFMF.050.1") (pin "2") (pinfunction "2_2") (pintype "passive"))
      (node (ref "Q1") (pin "1") (pinfunction "G_1") (pintype "bidirectional"))
      (node (ref "R1_PWRUSB") (pin "2") (pinfunction "2_2") (pintype "passive"))
      (node (ref "TP14") (pin "TP") (pinfunction "TP_TP") (pintype "input"))
    )
    (net (code "55") (name "VRTC") (class "Default")
      (node (ref "C10_SUPERCAP") (pin "2") (pinfunction "2_2") (pintype "passive"))
      (node (ref "C8") (pin "1") (pinfunction "1_1") (pintype "passive"))
      (node (ref "R_CAPACITOR") (pin "2") (pinfunction "2_2") (pintype "passive"))
      (node (ref "U3") (pin "14") (pinfunction "VBAT_14") (pintype "power_in"))
    )
    (net (code "56") (name "VUSB") (class "Default")
      (node (ref "J2") (pin "A4") (pinfunction "A4_A4") (pintype "bidirectional"))
      (node (ref "J2") (pin "A9") (pinfunction "A9_A9") (pintype "bidirectional"))
      (node (ref "J2") (pin "B4") (pinfunction "B4_B4") (pintype "bidirectional"))
      (node (ref "J2") (pin "B9") (pinfunction "B9_B9") (pintype "bidirectional"))
      (node (ref "PFMF.050.1") (pin "1") (pinfunction "1_1") (pintype "passive"))
    )
    (net (code "57") (name "unconnected-(IC1-NC-Pad4)") (class "Default")
      (node (ref "IC1") (pin "4") (pinfunction "NC_4") (pintype "no_connect"))
    )
    (net (code "58") (name "unconnected-(IC4-NC-Pad4)") (class "Default")
      (node (ref "IC4") (pin "4") (pinfunction "NC_4") (pintype "no_connect"))
    )
    (net (code "59") (name "unconnected-(J1-Pad1)") (class "Default")
      (node (ref "J1") (pin "1") (pinfunction "1_1") (pintype "bidirectional"))
    )
    (net (code "60") (name "unconnected-(J1-Pad6)") (class "Default")
      (node (ref "J1") (pin "6") (pinfunction "6_6") (pintype "bidirectional"))
    )
    (net (code "61") (name "unconnected-(J1-Pad7)") (class "Default")
      (node (ref "J1") (pin "7") (pinfunction "7_7") (pintype "bidirectional"))
    )
    (net (code "62") (name "unconnected-(J2-PadA8)") (class "Default")
      (node (ref "J2") (pin "A8") (pinfunction "A8_A8") (pintype "bidirectional"))
    )
    (net (code "63") (name "unconnected-(J2-PadB8)") (class "Default")
      (node (ref "J2") (pin "B8") (pinfunction "B8_B8") (pintype "bidirectional"))
    )
    (net (code "64") (name "unconnected-(J4-DAT1-PadP8)") (class "Default")
      (node (ref "J4") (pin "P8") (pinfunction "DAT1_P8") (pintype "bidirectional"))
    )
    (net (code "65") (name "unconnected-(J4-DAT2-PadP1)") (class "Default")
      (node (ref "J4") (pin "P1") (pinfunction "DAT2_P1") (pintype "bidirectional"))
    )
    (net (code "66") (name "unconnected-(J4-DETECTION_1-PadS1)") (class "Default")
      (node (ref "J4") (pin "S1") (pinfunction "DETECTION_1_S1") (pintype "bidirectional"))
    )
    (net (code "67") (name "unconnected-(J4-DETECTION_2-PadS2)") (class "Default")
      (node (ref "J4") (pin "S2") (pinfunction "DETECTION_2_S2") (pintype "bidirectional"))
    )
    (net (code "68") (name "unconnected-(U2-NC-Pad22)") (class "Default")
      (node (ref "U2") (pin "22") (pinfunction "NC_22") (pintype "no_connect"))
    )
    (net (code "69") (name "unconnected-(U4-~{ALERT}-Pad5)") (class "Default")
      (node (ref "U4") (pin "5") (pinfunction "~{ALERT}_5") (pintype "output"))
    )
  )
)
